# design.net
KiCad netlist of a schematic drawn in Altium Designer
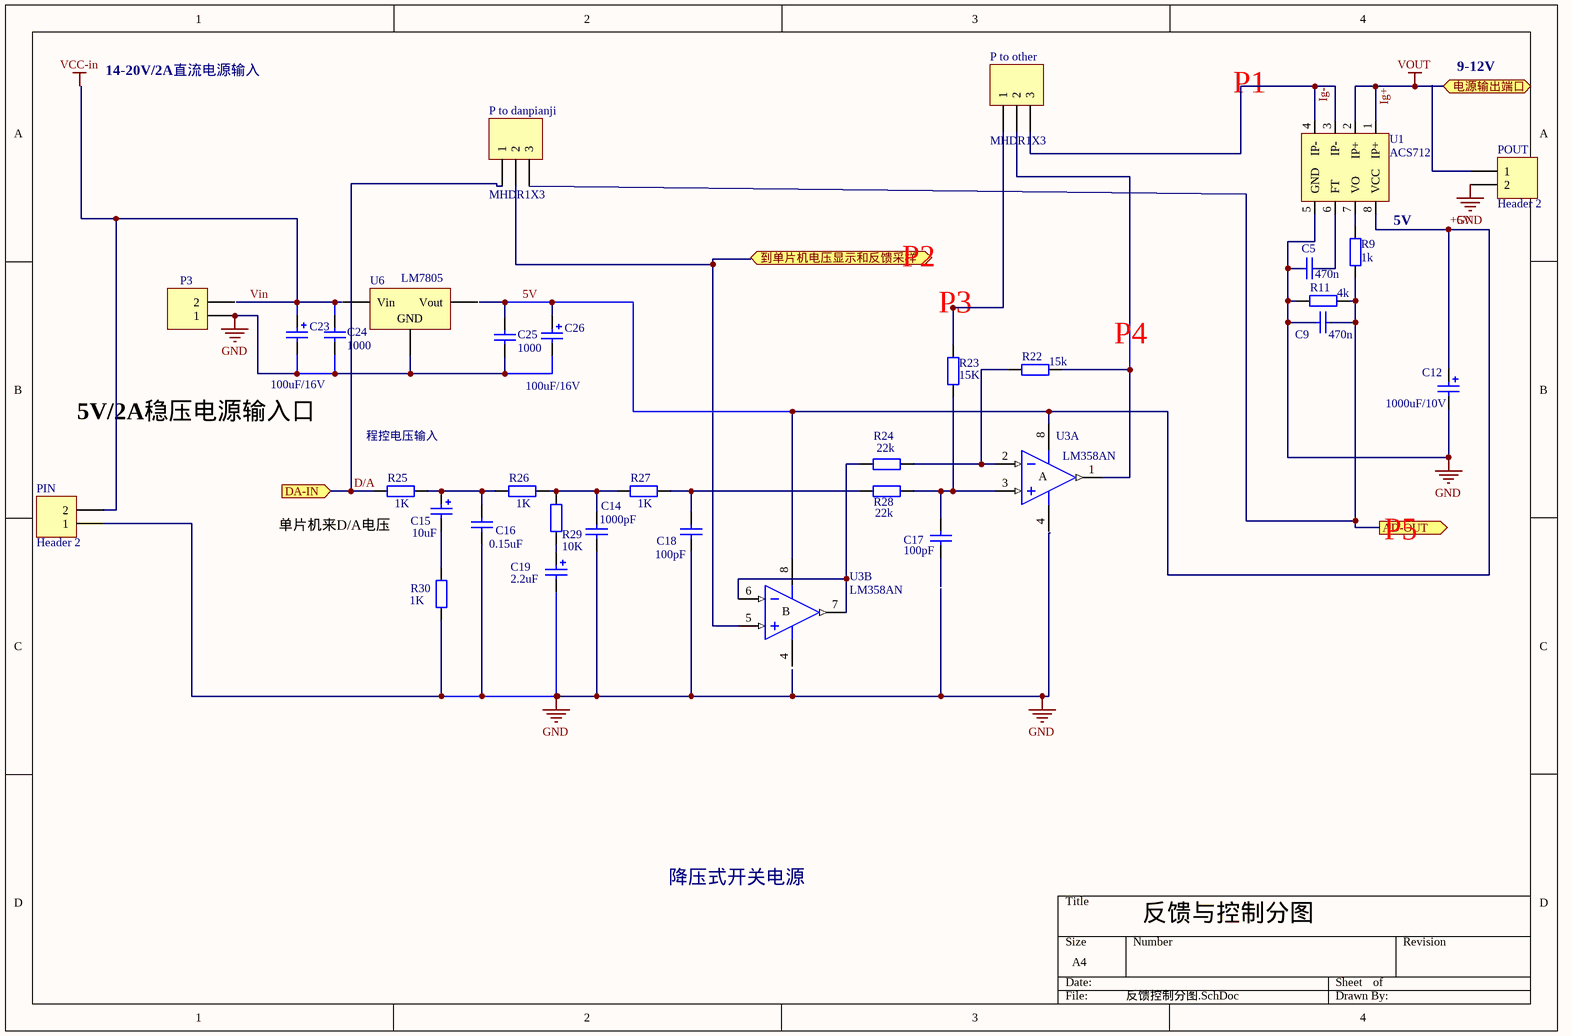
[diagram p0: 反馈控制分图.SchDoc]

(export (version "E")
  (design (tool "Eeschema 10.0.6"))
  (components
    (comp (ref "C5")
      (value "470n")
      (footprint "瓷片电容")
      (description "ECQ-U2A334ML")
      (fields (field (name "Comment") "275VAC") (field (name "PUBLISHER") "Altium Limited"))
      (libsource (lib "Sheet1") (part "Cap"))
    )
    (comp (ref "C9")
      (value "470n")
      (footprint "瓷片电容")
      (description "ECQ-U2A334ML")
      (fields (field (name "Comment") "275VAC") (field (name "PUBLISHER") "Altium Limited"))
      (libsource (lib "Sheet1") (part "Cap"))
    )
    (comp (ref "C12")
      (value "1000uF/10V")
      (footprint "100电解电容")
      (description "Polarized Capacitor (Axial)")
      (fields (field (name "Comment") "Cap Pol2") (field (name "PUBLISHER") "Altium Limited"))
      (libsource (lib "Miscellaneous Devices") (part "Cap Pol2"))
    )
    (comp (ref "C14")
      (value "1000pF")
      (footprint "瓷片电容")
      (description "Capacitor")
      (fields (field (name "Comment") "Cap") (field (name "PUBLISHER") "Altium Limited"))
      (libsource (lib "Miscellaneous Devices") (part "Cap"))
    )
    (comp (ref "C15")
      (value "10uF")
      (footprint "10uf")
      (description "Polarized Capacitor (Axial)")
      (fields (field (name "Comment") "Cap Pol2") (field (name "PUBLISHER") "Altium Limited"))
      (libsource (lib "Miscellaneous Devices") (part "Cap Pol2"))
    )
    (comp (ref "C16")
      (value "0.15uF")
      (footprint "瓷片电容")
      (description "Capacitor")
      (fields (field (name "Comment") "Cap") (field (name "PUBLISHER") "Altium Limited"))
      (libsource (lib "Miscellaneous Devices") (part "Cap"))
    )
    (comp (ref "C17")
      (value "100pF")
      (footprint "瓷片电容")
      (description "Capacitor (Semiconductor SIM Model)")
      (fields (field (name "Comment") "Cap Semi") (field (name "PUBLISHER") "Altium Limited"))
      (libsource (lib "Miscellaneous Devices") (part "Cap Semi"))
    )
    (comp (ref "C18")
      (value "100pF")
      (footprint "瓷片电容")
      (description "Capacitor")
      (fields (field (name "Comment") "Cap") (field (name "PUBLISHER") "Altium Limited"))
      (libsource (lib "Miscellaneous Devices") (part "Cap"))
    )
    (comp (ref "C19")
      (value "2.2uF")
      (footprint "10uf")
      (description "Polarized Capacitor (Axial)")
      (fields (field (name "Comment") "Cap Pol2") (field (name "PUBLISHER") "Altium Limited"))
      (libsource (lib "Miscellaneous Devices") (part "Cap Pol2"))
    )
    (comp (ref "C23")
      (value "100uF/16V")
      (footprint "100电解电容")
      (description "Polarized Capacitor (Axial)")
      (fields (field (name "Comment") "Cap Pol2") (field (name "PUBLISHER") "Altium Limited"))
      (libsource (lib "Miscellaneous Devices") (part "Cap Pol2"))
    )
    (comp (ref "C24")
      (value "1000")
      (footprint "瓷片电容")
      (description "Capacitor")
      (fields (field (name "Comment") "Cap") (field (name "PUBLISHER") "Altium Limited"))
      (libsource (lib "Miscellaneous Devices") (part "Cap"))
    )
    (comp (ref "C25")
      (value "1000")
      (footprint "瓷片电容")
      (description "Capacitor")
      (fields (field (name "Comment") "Cap") (field (name "PUBLISHER") "Altium Limited"))
      (libsource (lib "Miscellaneous Devices") (part "Cap"))
    )
    (comp (ref "C26")
      (value "100uF/16V")
      (footprint "100电解电容")
      (description "Polarized Capacitor (Axial)")
      (fields (field (name "Comment") "Cap Pol2") (field (name "PUBLISHER") "Altium Limited"))
      (libsource (lib "Miscellaneous Devices") (part "Cap Pol2"))
    )
    (comp (ref "P to danpianji")
      (value "MHDR1X3")
      (footprint "MHDR1X3")
      (description "Header, 3-Pin")
      (fields (field (name "PUBLISHER") "Altium Limited"))
      (libsource (lib "Miscellaneous Connectors") (part "MHDR1X3"))
    )
    (comp (ref "P to other")
      (value "MHDR1X3")
      (footprint "MHDR1X3")
      (description "Header, 3-Pin")
      (fields (field (name "PUBLISHER") "Altium Limited"))
      (libsource (lib "Miscellaneous Connectors") (part "MHDR1X3"))
    )
    (comp (ref "P3")
      (value "MHDR1X2")
      (footprint "MHDR1X2")
      (description "Header, 2-Pin")
      (fields (field (name "PUBLISHER") "Altium Limited"))
      (libsource (lib "Miscellaneous Connectors") (part "MHDR1X2"))
    )
    (comp (ref "PIN")
      (value "Header 2")
      (footprint "HDR1X2")
      (description "Header, 2-Pin")
      (fields (field (name "PUBLISHER") "Altium Limited"))
      (libsource (lib "Miscellaneous Connectors") (part "Header 2"))
    )
    (comp (ref "POUT")
      (value "Header 2")
      (footprint "HDR1X2")
      (description "Header, 2-Pin")
      (fields (field (name "PUBLISHER") "Altium Limited"))
      (libsource (lib "") (part "Header 2_1"))
    )
    (comp (ref "R9")
      (value "1k")
      (footprint "AXIAL-0.3")
      (description "Resistor")
      (fields (field (name "Comment") "Res2") (field (name "PUBLISHER") "Altium Limited"))
      (libsource (lib "") (part "Res2_1"))
    )
    (comp (ref "R11")
      (value "4k")
      (footprint "AXIAL-0.3")
      (description "Resistor")
      (fields (field (name "Comment") "Res2") (field (name "PUBLISHER") "Altium Limited"))
      (libsource (lib "Miscellaneous Devices") (part "Res2"))
    )
    (comp (ref "R22")
      (value "15k")
      (footprint "AXIAL-0.3")
      (description "Resistor")
      (fields (field (name "Comment") "Res2") (field (name "PUBLISHER") "Altium Limited"))
      (libsource (lib "Miscellaneous Devices") (part "Res2"))
    )
    (comp (ref "R23")
      (value "15K")
      (footprint "AXIAL-0.4")
      (description "Resistor")
      (fields (field (name "Comment") "Res2") (field (name "PUBLISHER") "Altium Limited"))
      (libsource (lib "") (part "Res2_1"))
    )
    (comp (ref "R24")
      (value "22k")
      (footprint "AXIAL-0.3")
      (description "Resistor")
      (fields (field (name "Comment") "Res2") (field (name "PUBLISHER") "Altium Limited"))
      (libsource (lib "Miscellaneous Devices") (part "Res2"))
    )
    (comp (ref "R25")
      (value "1K")
      (footprint "AXIAL-0.4")
      (description "Resistor")
      (fields (field (name "Comment") "Res2") (field (name "PUBLISHER") "Altium Limited"))
      (libsource (lib "Miscellaneous Devices") (part "Res2"))
    )
    (comp (ref "R26")
      (value "1K")
      (footprint "AXIAL-0.4")
      (description "Resistor")
      (fields (field (name "Comment") "Res2") (field (name "PUBLISHER") "Altium Limited"))
      (libsource (lib "Miscellaneous Devices") (part "Res2"))
    )
    (comp (ref "R27")
      (value "1K")
      (footprint "AXIAL-0.4")
      (description "Resistor")
      (fields (field (name "Comment") "Res2") (field (name "PUBLISHER") "Altium Limited"))
      (libsource (lib "Miscellaneous Devices") (part "Res2"))
    )
    (comp (ref "R28")
      (value "22k")
      (footprint "AXIAL-0.3")
      (description "Resistor")
      (fields (field (name "Comment") "Res2") (field (name "PUBLISHER") "Altium Limited"))
      (libsource (lib "Miscellaneous Devices") (part "Res2"))
    )
    (comp (ref "R29")
      (value "10K")
      (footprint "AXIAL-0.4")
      (description "Resistor")
      (fields (field (name "Comment") "Res2") (field (name "PUBLISHER") "Altium Limited"))
      (libsource (lib "") (part "Res2_1"))
    )
    (comp (ref "R30")
      (value "1K")
      (footprint "AXIAL-0.4")
      (description "Resistor")
      (fields (field (name "Comment") "Res2") (field (name "PUBLISHER") "Altium Limited"))
      (libsource (lib "") (part "Res2_1"))
    )
    (comp (ref "U1") (value "ACS712") (footprint "HDR2X4") (libsource (lib "Sheet1") (part "ACS712")))
    (comp (ref "U3")
      (value "LM358AN")
      (footprint "HDR2X4_CEN")
      (description "Low-Power Quad Operational Amplifier")
      (fields (field (name "PUBLISHER") "Altium Limited"))
      (libsource (lib "ST Operational Amplifier") (part "LM324AN"))
    )
    (comp (ref "U6")
      (value "LM7805")
      (footprint "TO-220-AB")
      (description "Voltage Regulator")
      (fields (field (name "PUBLISHER") "Altium Limited"))
      (libsource (lib "Miscellaneous Devices") (part "Volt Reg"))
    )
  )
  (nets
    (net (code "2") (name "/5V") (class "Default")
      (node (ref "C12") (pin "1") (pinfunction "1_1") (pintype "passive"))
      (node (ref "C25") (pin "2") (pinfunction "2_2") (pintype "passive"))
      (node (ref "C26") (pin "1") (pinfunction "1_1") (pintype "passive"))
      (node (ref "U1") (pin "8") (pinfunction "VCC_8") (pintype "passive"))
      (node (ref "U3") (pin "8") (pinfunction "V+_8") (pintype "power_in"))
    )
    (net (code "3") (name "/AD-OUT") (class "Default")
      (node (ref "C9") (pin "1") (pinfunction "1_1") (pintype "passive"))
      (node (ref "P to danpianji") (pin "3") (pinfunction "3_3") (pintype "passive"))
      (node (ref "R11") (pin "2") (pinfunction "2_2") (pintype "passive"))
      (node (ref "R9") (pin "1") (pinfunction "1_1") (pintype "passive"))
    )
    (net (code "4") (name "/D{slash}A") (class "Default")
      (node (ref "P to danpianji") (pin "1") (pinfunction "1_1") (pintype "passive"))
      (node (ref "R25") (pin "1") (pinfunction "1_1") (pintype "passive"))
    )
    (net (code "5") (name "/Ig-") (class "Default")
      (node (ref "P to other") (pin "3") (pinfunction "3_3") (pintype "passive"))
      (node (ref "U1") (pin "3") (pinfunction "IP-_3") (pintype "passive"))
      (node (ref "U1") (pin "4") (pinfunction "IP-_4") (pintype "passive"))
    )
    (net (code "6") (name "/Vin") (class "Default")
      (node (ref "C23") (pin "1") (pinfunction "1_1") (pintype "passive"))
      (node (ref "C24") (pin "2") (pinfunction "2_2") (pintype "passive"))
      (node (ref "PIN") (pin "2") (pinfunction "2_2") (pintype "passive"))
    )
    (net (code "8") (name "GND") (class "Default")
      (node (ref "C12") (pin "2") (pinfunction "2_2") (pintype "passive"))
      (node (ref "C14") (pin "1") (pinfunction "1_1") (pintype "passive"))
      (node (ref "C18") (pin "1") (pinfunction "1_1") (pintype "passive"))
      (node (ref "C19") (pin "2") (pinfunction "2_2") (pintype "passive"))
      (node (ref "C23") (pin "2") (pinfunction "2_2") (pintype "passive"))
      (node (ref "C24") (pin "1") (pinfunction "1_1") (pintype "passive"))
      (node (ref "C25") (pin "1") (pinfunction "1_1") (pintype "passive"))
      (node (ref "C26") (pin "2") (pinfunction "2_2") (pintype "passive"))
      (node (ref "C5") (pin "1") (pinfunction "1_1") (pintype "passive"))
      (node (ref "C9") (pin "2") (pinfunction "2_2") (pintype "passive"))
      (node (ref "P3") (pin "1") (pinfunction "1_1") (pintype "passive"))
      (node (ref "POUT") (pin "2") (pinfunction "2_2") (pintype "passive"))
      (node (ref "R11") (pin "1") (pinfunction "1_1") (pintype "passive"))
      (node (ref "U1") (pin "5") (pinfunction "GND_5") (pintype "passive"))
      (node (ref "U6") (pin "2") (pinfunction "GND_2") (pintype "passive"))
    )
    (net (code "9") (name "Net-(C14-Pad2)") (class "Default")
      (node (ref "C14") (pin "2") (pinfunction "2_2") (pintype "passive"))
      (node (ref "R26") (pin "2") (pinfunction "2_2") (pintype "passive"))
      (node (ref "R27") (pin "1") (pinfunction "1_1") (pintype "passive"))
      (node (ref "R29") (pin "2") (pinfunction "2_2") (pintype "passive"))
    )
    (net (code "10") (name "Net-(C15-Pad1)") (class "Default")
      (node (ref "C15") (pin "1") (pinfunction "1_1") (pintype "passive"))
      (node (ref "C16") (pin "2") (pinfunction "2_2") (pintype "passive"))
      (node (ref "R25") (pin "2") (pinfunction "2_2") (pintype "passive"))
      (node (ref "R26") (pin "1") (pinfunction "1_1") (pintype "passive"))
    )
    (net (code "11") (name "Net-(C15-Pad2)") (class "Default")
      (node (ref "C15") (pin "2") (pinfunction "2_2") (pintype "passive"))
      (node (ref "R30") (pin "2") (pinfunction "2_2") (pintype "passive"))
    )
    (net (code "12") (name "Net-(C16-Pad1)") (class "Default")
      (node (ref "C16") (pin "1") (pinfunction "1_1") (pintype "passive"))
      (node (ref "PIN") (pin "1") (pinfunction "1_1") (pintype "passive"))
      (node (ref "R30") (pin "1") (pinfunction "1_1") (pintype "passive"))
    )
    (net (code "13") (name "Net-(C18-Pad2)") (class "Default")
      (node (ref "C18") (pin "2") (pinfunction "2_2") (pintype "passive"))
      (node (ref "R27") (pin "2") (pinfunction "2_2") (pintype "passive"))
      (node (ref "R28") (pin "1") (pinfunction "1_1") (pintype "passive"))
    )
    (net (code "14") (name "Net-(C19-Pad1)") (class "Default")
      (node (ref "C19") (pin "1") (pinfunction "1_1") (pintype "passive"))
      (node (ref "R29") (pin "1") (pinfunction "1_1") (pintype "passive"))
    )
    (net (code "15") (name "Net-(P to other-Pad1)") (class "Default")
      (node (ref "P to other") (pin "1") (pinfunction "1_1") (pintype "passive"))
      (node (ref "R23") (pin "2") (pinfunction "2_2") (pintype "passive"))
    )
    (net (code "16") (name "Net-(U1-FT)") (class "Default")
      (node (ref "C5") (pin "2") (pinfunction "2_2") (pintype "passive"))
      (node (ref "U1") (pin "6") (pinfunction "FT_6") (pintype "passive"))
    )
    (net (code "17") (name "Net-(U1-VO)") (class "Default")
      (node (ref "R9") (pin "2") (pinfunction "2_2") (pintype "passive"))
      (node (ref "U1") (pin "7") (pinfunction "VO_7") (pintype "passive"))
    )
    (net (code "18") (name "Net-(U3A-IN+)") (class "Default")
      (node (ref "C17") (pin "2") (pinfunction "2_2") (pintype "passive"))
      (node (ref "R23") (pin "1") (pinfunction "1_1") (pintype "passive"))
      (node (ref "R28") (pin "2") (pinfunction "2_2") (pintype "passive"))
      (node (ref "U3") (pin "3") (pinfunction "IN+_3") (pintype "input"))
    )
    (net (code "19") (name "Net-(U3A-IN-)") (class "Default")
      (node (ref "R22") (pin "1") (pinfunction "1_1") (pintype "passive"))
      (node (ref "R24") (pin "2") (pinfunction "2_2") (pintype "passive"))
      (node (ref "U3") (pin "2") (pinfunction "IN-_2") (pintype "input"))
    )
    (net (code "20") (name "Net-(U3A-OUT)") (class "Default")
      (node (ref "P to other") (pin "2") (pinfunction "2_2") (pintype "passive"))
      (node (ref "R22") (pin "2") (pinfunction "2_2") (pintype "passive"))
      (node (ref "U3") (pin "1") (pinfunction "OUT_1") (pintype "output"))
    )
    (net (code "21") (name "Net-(U3B-IN+)") (class "Default")
      (node (ref "P to danpianji") (pin "2") (pinfunction "2_2") (pintype "passive"))
      (node (ref "U3") (pin "5") (pinfunction "IN+_5") (pintype "input"))
    )
    (net (code "22") (name "Net-(U3B-IN-)") (class "Default")
      (node (ref "R24") (pin "1") (pinfunction "1_1") (pintype "passive"))
      (node (ref "U3") (pin "6") (pinfunction "IN-_6") (pintype "input"))
      (node (ref "U3") (pin "7") (pinfunction "OUT_7") (pintype "output"))
    )
    (net (code "24") (name "VOUT") (class "Default")
      (node (ref "U1") (pin "1") (pinfunction "IP+_1") (pintype "passive"))
      (node (ref "U1") (pin "2") (pinfunction "IP+_2") (pintype "passive"))
    )
    (net (code "25") (name "unconnected-(C17-Pad1)") (class "Default")
      (node (ref "C17") (pin "1") (pinfunction "1_1") (pintype "passive"))
    )
    (net (code "26") (name "unconnected-(P3-Pad2)") (class "Default")
      (node (ref "P3") (pin "2") (pinfunction "2_2") (pintype "passive"))
    )
    (net (code "27") (name "unconnected-(POUT-Pad1)") (class "Default")
      (node (ref "POUT") (pin "1") (pinfunction "1_1") (pintype "passive"))
    )
    (net (code "28") (name "unconnected-(U3A-V--Pad4)") (class "Default")
      (node (ref "U3") (pin "4") (pinfunction "V-_4") (pintype "power_in"))
    )
    (net (code "29") (name "unconnected-(U3B-V--Pad4)") (class "Default")
      (node (ref "U3") (pin "4") (pinfunction "V-_4") (pintype "power_in"))
    )
    (net (code "30") (name "unconnected-(U6-Vin-Pad1)") (class "Default")
      (node (ref "U6") (pin "1") (pinfunction "Vin_1") (pintype "passive"))
    )
    (net (code "31") (name "unconnected-(U6-Vout-Pad3)") (class "Default")
      (node (ref "U6") (pin "3") (pinfunction "Vout_3") (pintype "passive"))
    )
  )
)
